# NotSoSmartWatch-BASIC-BOTTOM.net
KiCad netlist of a schematic drawn in EAGLE
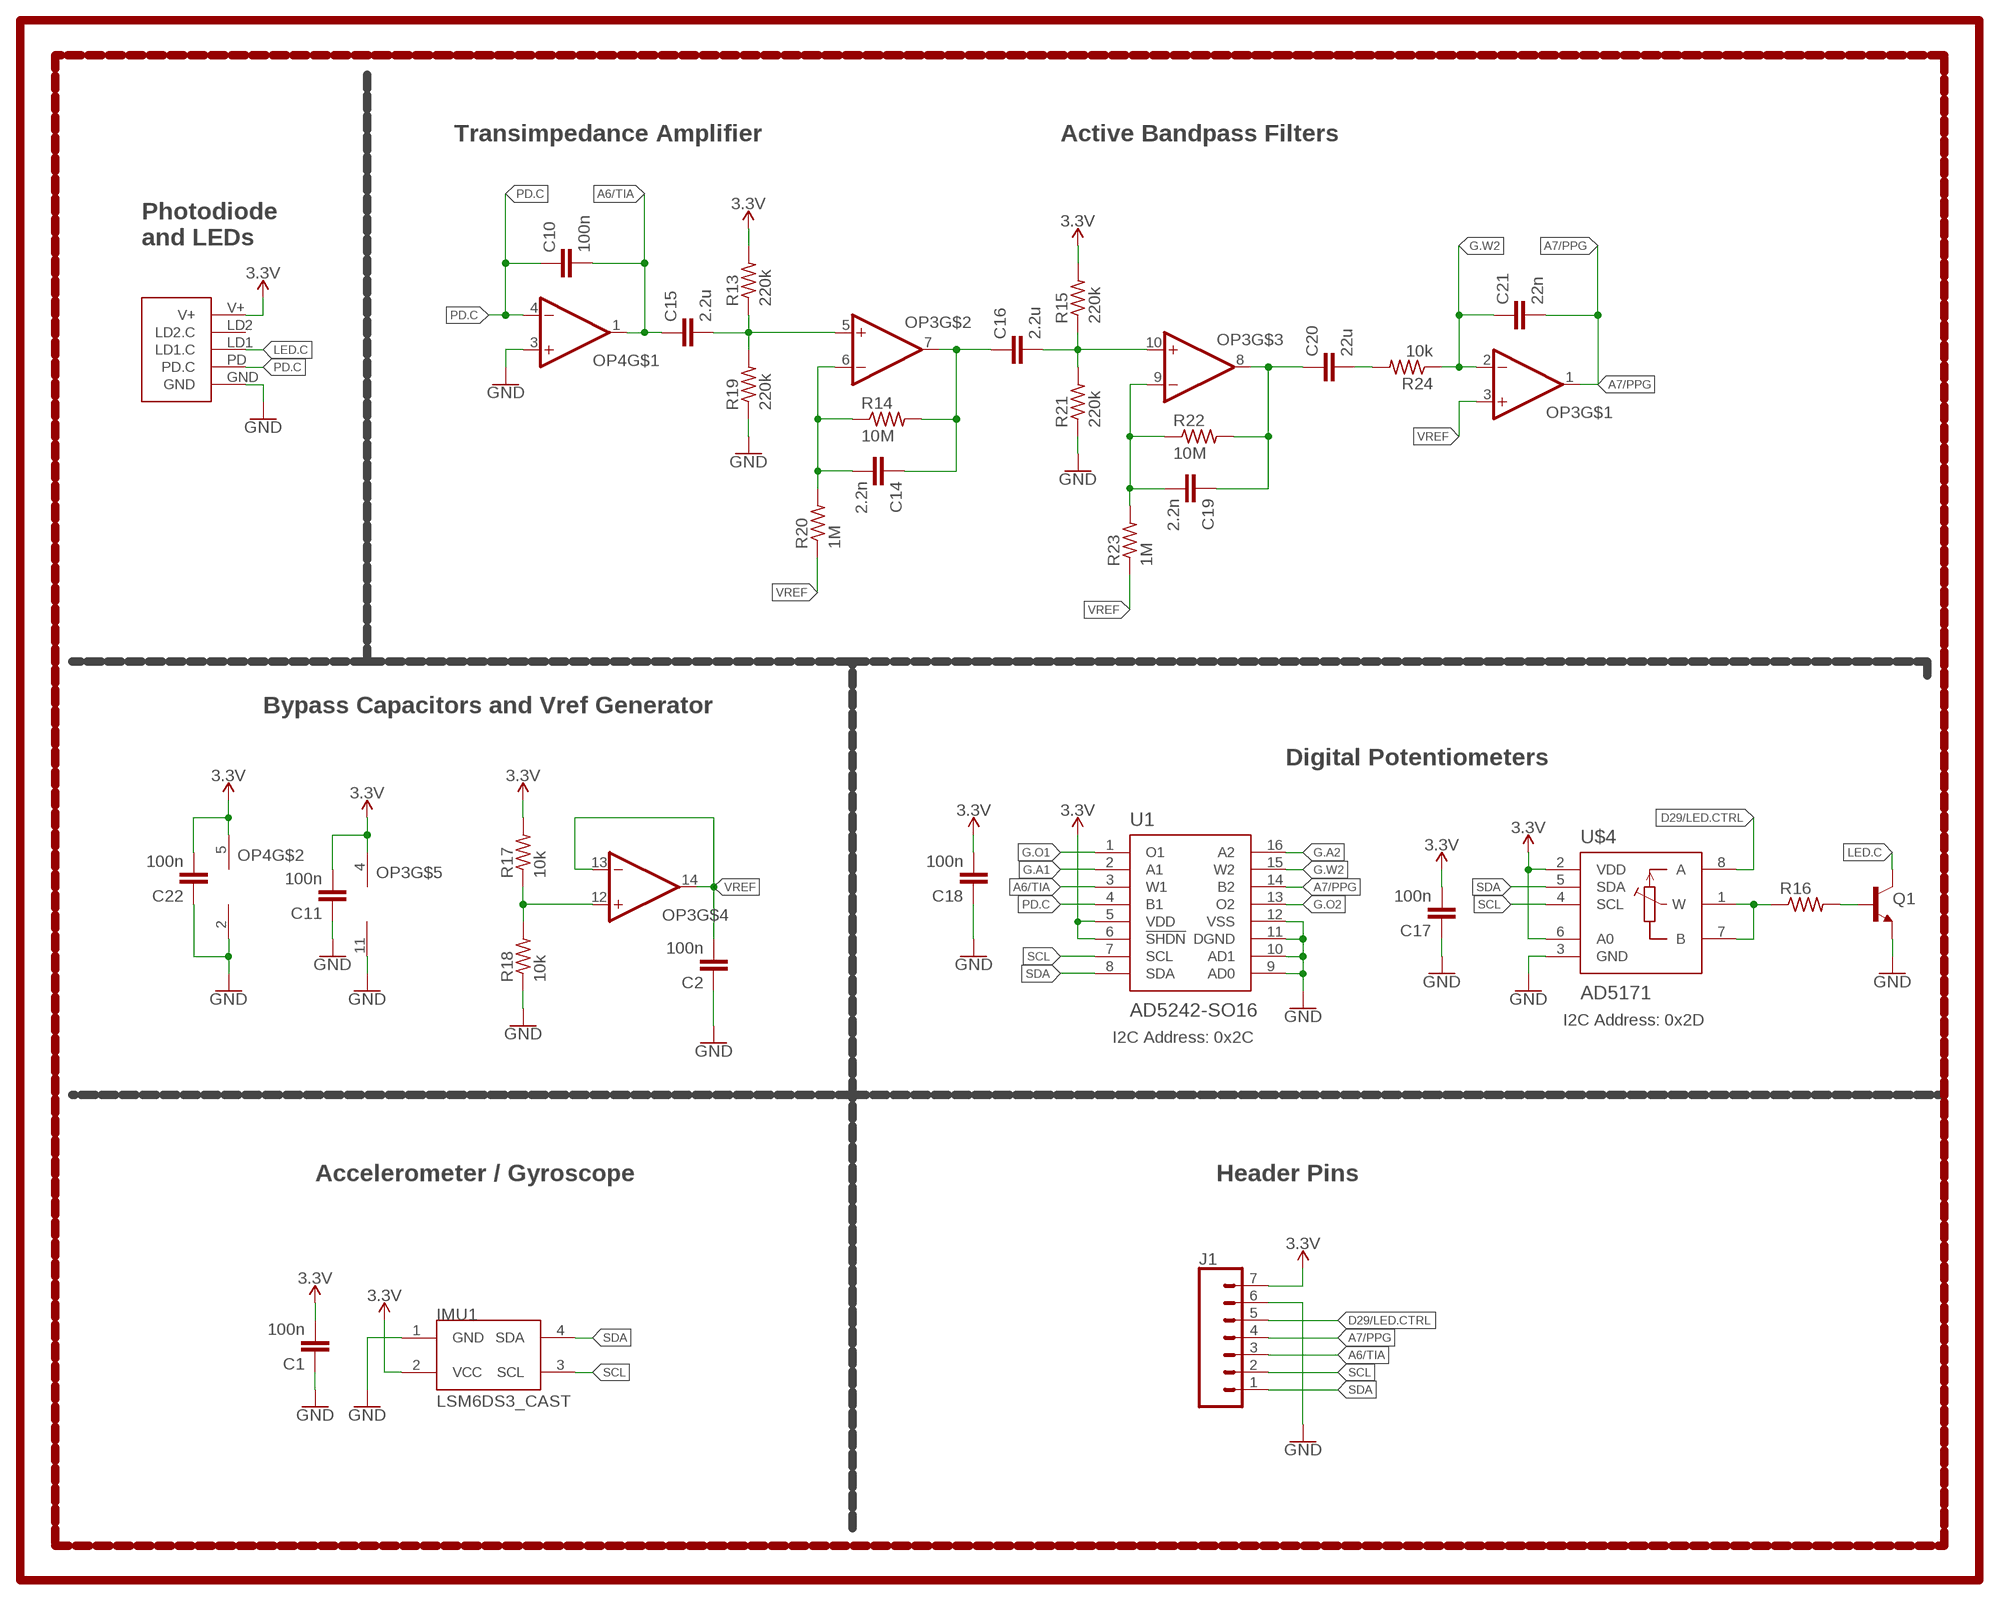
[diagram p0: schematic, sheet 1]

(export (version "E")
  (design (tool "Eeschema 10.0.6"))
  (components
    (comp (ref "C1")
      (value "100n")
      (footprint "eagle-import:C0603")
      (libsource (lib "eagle-import") (part "CAPACITOR0603"))
    )
    (comp (ref "C2")
      (value "100n")
      (footprint "eagle-import:C0603")
      (libsource (lib "eagle-import") (part "CAPACITOR0603"))
    )
    (comp (ref "C10")
      (value "100n")
      (footprint "eagle-import:C0603")
      (libsource (lib "eagle-import") (part "CAPACITOR0603"))
    )
    (comp (ref "C11")
      (value "100n")
      (footprint "eagle-import:C0603")
      (libsource (lib "eagle-import") (part "CAPACITOR0603"))
    )
    (comp (ref "C14")
      (value "2.2n")
      (footprint "eagle-import:C0603")
      (libsource (lib "eagle-import") (part "CAPACITOR0603"))
    )
    (comp (ref "C15")
      (value "2.2u")
      (footprint "eagle-import:C0603")
      (libsource (lib "eagle-import") (part "CAPACITOR0603"))
    )
    (comp (ref "C16")
      (value "2.2u")
      (footprint "eagle-import:C0603")
      (libsource (lib "eagle-import") (part "CAPACITOR0603"))
    )
    (comp (ref "C17")
      (value "100n")
      (footprint "eagle-import:C0603")
      (libsource (lib "eagle-import") (part "CAPACITOR0603"))
    )
    (comp (ref "C18")
      (value "100n")
      (footprint "eagle-import:C0603")
      (libsource (lib "eagle-import") (part "CAPACITOR0603"))
    )
    (comp (ref "C19")
      (value "2.2n")
      (footprint "eagle-import:C0603")
      (libsource (lib "eagle-import") (part "CAPACITOR0603"))
    )
    (comp (ref "C20")
      (value "22u")
      (footprint "eagle-import:C0603")
      (libsource (lib "eagle-import") (part "CAPACITOR0603"))
    )
    (comp (ref "C21")
      (value "22n")
      (footprint "eagle-import:C0603")
      (libsource (lib "eagle-import") (part "CAPACITOR0603"))
    )
    (comp (ref "C22")
      (value "100n")
      (footprint "eagle-import:C0603")
      (libsource (lib "eagle-import") (part "CAPACITOR0603"))
    )
    (comp (ref "IMU1")
      (value "LSM6DS3_CAST")
      (footprint "eagle-import:LSM6DS3_CAST")
      (libsource (lib "eagle-import") (part "LSM6DS3_CAST"))
    )
    (comp (ref "J1")
      (value "CONN_07-1.27MM")
      (footprint "eagle-import:1X07_1.27MM")
      (libsource (lib "eagle-import") (part "CONN_07-1.27MM"))
    )
    (comp (ref "OP3")
      (value "OP-QUAD-SO14")
      (footprint "eagle-import:SO14")
      (libsource (lib "eagle-import") (part "OP-QUAD-SO14"))
    )
    (comp (ref "OP4")
      (value "OP-SINGLEOT")
      (footprint "eagle-import:SOT23-5")
      (libsource (lib "eagle-import") (part "OP-SINGLEOT"))
    )
    (comp (ref "Q1")
      (value "NPN-GENERIC")
      (footprint "eagle-import:SOT23-3")
      (libsource (lib "eagle-import") (part "NPN-GENERIC"))
    )
    (comp (ref "R13")
      (value "220k")
      (footprint "eagle-import:R0603")
      (libsource (lib "eagle-import") (part "RESISTOR0603"))
    )
    (comp (ref "R14")
      (value "10M")
      (footprint "eagle-import:R0603")
      (libsource (lib "eagle-import") (part "RESISTOR0603"))
    )
    (comp (ref "R15")
      (value "220k")
      (footprint "eagle-import:R0603")
      (libsource (lib "eagle-import") (part "RESISTOR0603"))
    )
    (comp (ref "R16")
      (value "RESISTOR0603")
      (footprint "eagle-import:R0603")
      (libsource (lib "eagle-import") (part "RESISTOR0603"))
    )
    (comp (ref "R17")
      (value "10k")
      (footprint "eagle-import:R0402")
      (libsource (lib "eagle-import") (part "RESISTOR0402"))
    )
    (comp (ref "R18")
      (value "10k")
      (footprint "eagle-import:R0402")
      (libsource (lib "eagle-import") (part "RESISTOR0402"))
    )
    (comp (ref "R19")
      (value "220k")
      (footprint "eagle-import:R0603")
      (libsource (lib "eagle-import") (part "RESISTOR0603"))
    )
    (comp (ref "R20")
      (value "1M")
      (footprint "eagle-import:R0603")
      (libsource (lib "eagle-import") (part "RESISTOR0603"))
    )
    (comp (ref "R21")
      (value "220k")
      (footprint "eagle-import:R0603")
      (libsource (lib "eagle-import") (part "RESISTOR0603"))
    )
    (comp (ref "R22")
      (value "10M")
      (footprint "eagle-import:R0603")
      (libsource (lib "eagle-import") (part "RESISTOR0603"))
    )
    (comp (ref "R23")
      (value "1M")
      (footprint "eagle-import:R0603")
      (libsource (lib "eagle-import") (part "RESISTOR0603"))
    )
    (comp (ref "R24")
      (value "10k")
      (footprint "eagle-import:R0603")
      (libsource (lib "eagle-import") (part "RESISTOR0603"))
    )
    (comp (ref "U$3")
      (value "PPG.MODULE.2")
      (footprint "eagle-import:PPG.MODULE.2")
      (libsource (lib "eagle-import") (part "PPG.MODULE.2"))
    )
    (comp (ref "U$4")
      (value "AD5171")
      (footprint "eagle-import:SOT-23-8")
      (libsource (lib "eagle-import") (part "AD5171"))
    )
    (comp (ref "U1")
      (value "AD5242-SO16")
      (footprint "eagle-import:SO16")
      (libsource (lib "eagle-import") (part "AD5242-SO16"))
    )
  )
  (nets
    (net (code "1") (name "3.3V") (class "Default")
      (node (ref "C1") (pin "2") (pinfunction "2_2") (pintype "passive"))
      (node (ref "C11") (pin "2") (pinfunction "2_2") (pintype "passive"))
      (node (ref "C17") (pin "2") (pinfunction "2_2") (pintype "passive"))
      (node (ref "C18") (pin "2") (pinfunction "2_2") (pintype "passive"))
      (node (ref "C22") (pin "2") (pinfunction "2_2") (pintype "passive"))
      (node (ref "IMU1") (pin "2") (pinfunction "VCC_2") (pintype "bidirectional"))
      (node (ref "J1") (pin "7") (pinfunction "7_7") (pintype "passive"))
      (node (ref "OP3") (pin "4") (pinfunction "V+_4") (pintype "power_in"))
      (node (ref "OP4") (pin "5") (pinfunction "V+_5") (pintype "power_in"))
      (node (ref "R13") (pin "2") (pinfunction "2_2") (pintype "passive"))
      (node (ref "R15") (pin "2") (pinfunction "2_2") (pintype "passive"))
      (node (ref "R17") (pin "2") (pinfunction "2_2") (pintype "passive"))
      (node (ref "U$3") (pin "V+") (pinfunction "V+_V+") (pintype "bidirectional"))
      (node (ref "U$4") (pin "2") (pinfunction "VDD_2") (pintype "bidirectional"))
      (node (ref "U$4") (pin "6") (pinfunction "A0_6") (pintype "bidirectional"))
      (node (ref "U1") (pin "5") (pinfunction "VDD_5") (pintype "bidirectional"))
      (node (ref "U1") (pin "6") (pinfunction "~{SHDN}_6") (pintype "bidirectional"))
    )
    (net (code "2") (name "A6{slash}TIA") (class "Default")
      (node (ref "C10") (pin "2") (pinfunction "2_2") (pintype "passive"))
      (node (ref "C15") (pin "1") (pinfunction "1_1") (pintype "passive"))
      (node (ref "J1") (pin "3") (pinfunction "3_3") (pintype "passive"))
      (node (ref "OP4") (pin "1") (pinfunction "OUT_1") (pintype "output"))
      (node (ref "U1") (pin "3") (pinfunction "W1_3") (pintype "bidirectional"))
    )
    (net (code "3") (name "A7{slash}PPG") (class "Default")
      (node (ref "C21") (pin "2") (pinfunction "2_2") (pintype "passive"))
      (node (ref "J1") (pin "4") (pinfunction "4_4") (pintype "passive"))
      (node (ref "OP3") (pin "1") (pinfunction "OUT_1") (pintype "output"))
      (node (ref "U1") (pin "14") (pinfunction "B2_14") (pintype "bidirectional"))
    )
    (net (code "4") (name "D29{slash}LED.CTRL") (class "Default")
      (node (ref "J1") (pin "5") (pinfunction "5_5") (pintype "passive"))
      (node (ref "U$4") (pin "8") (pinfunction "A_8") (pintype "bidirectional"))
    )
    (net (code "5") (name "G.A1") (class "Default")
      (node (ref "U1") (pin "2") (pinfunction "A1_2") (pintype "bidirectional"))
    )
    (net (code "6") (name "G.A2") (class "Default")
      (node (ref "U1") (pin "16") (pinfunction "A2_16") (pintype "bidirectional"))
    )
    (net (code "7") (name "G.O1") (class "Default")
      (node (ref "U1") (pin "1") (pinfunction "O1_1") (pintype "bidirectional"))
    )
    (net (code "8") (name "G.O2") (class "Default")
      (node (ref "U1") (pin "13") (pinfunction "O2_13") (pintype "bidirectional"))
    )
    (net (code "9") (name "G.W2") (class "Default")
      (node (ref "C21") (pin "1") (pinfunction "1_1") (pintype "passive"))
      (node (ref "OP3") (pin "2") (pinfunction "-IN_2") (pintype "input"))
      (node (ref "R24") (pin "1") (pinfunction "1_1") (pintype "passive"))
      (node (ref "U1") (pin "15") (pinfunction "W2_15") (pintype "bidirectional"))
    )
    (net (code "10") (name "GND") (class "Default")
      (node (ref "C1") (pin "1") (pinfunction "1_1") (pintype "passive"))
      (node (ref "C11") (pin "1") (pinfunction "1_1") (pintype "passive"))
      (node (ref "C17") (pin "1") (pinfunction "1_1") (pintype "passive"))
      (node (ref "C18") (pin "1") (pinfunction "1_1") (pintype "passive"))
      (node (ref "C2") (pin "1") (pinfunction "1_1") (pintype "passive"))
      (node (ref "C22") (pin "1") (pinfunction "1_1") (pintype "passive"))
      (node (ref "IMU1") (pin "1") (pinfunction "GND_1") (pintype "bidirectional"))
      (node (ref "J1") (pin "6") (pinfunction "6_6") (pintype "passive"))
      (node (ref "OP3") (pin "11") (pinfunction "V-_11") (pintype "power_in"))
      (node (ref "OP4") (pin "2") (pinfunction "V-_2") (pintype "power_in"))
      (node (ref "OP4") (pin "3") (pinfunction "+IN_3") (pintype "input"))
      (node (ref "Q1") (pin "2") (pinfunction "E_2") (pintype "passive"))
      (node (ref "R18") (pin "1") (pinfunction "1_1") (pintype "passive"))
      (node (ref "R19") (pin "1") (pinfunction "1_1") (pintype "passive"))
      (node (ref "R21") (pin "1") (pinfunction "1_1") (pintype "passive"))
      (node (ref "U$3") (pin "GND") (pinfunction "GND_GND") (pintype "bidirectional"))
      (node (ref "U$4") (pin "3") (pinfunction "GND_3") (pintype "bidirectional"))
      (node (ref "U1") (pin "10") (pinfunction "AD1_10") (pintype "bidirectional"))
      (node (ref "U1") (pin "11") (pinfunction "DGND_11") (pintype "bidirectional"))
      (node (ref "U1") (pin "12") (pinfunction "VSS_12") (pintype "bidirectional"))
      (node (ref "U1") (pin "9") (pinfunction "AD0_9") (pintype "bidirectional"))
    )
    (net (code "11") (name "LED.C") (class "Default")
      (node (ref "Q1") (pin "3") (pinfunction "C_3") (pintype "passive"))
      (node (ref "U$3") (pin "LD1") (pinfunction "LD1.C_LD1") (pintype "bidirectional"))
    )
    (net (code "12") (name "Net-(C20-Pad2)") (class "Default")
      (node (ref "C20") (pin "2") (pinfunction "2_2") (pintype "passive"))
      (node (ref "R24") (pin "2") (pinfunction "2_2") (pintype "passive"))
    )
    (net (code "13") (name "Net-(OP3B-+IN)") (class "Default")
      (node (ref "C15") (pin "2") (pinfunction "2_2") (pintype "passive"))
      (node (ref "OP3") (pin "5") (pinfunction "+IN_5") (pintype "input"))
      (node (ref "R13") (pin "1") (pinfunction "1_1") (pintype "passive"))
      (node (ref "R19") (pin "2") (pinfunction "2_2") (pintype "passive"))
    )
    (net (code "14") (name "Net-(OP3B--IN)") (class "Default")
      (node (ref "C14") (pin "2") (pinfunction "2_2") (pintype "passive"))
      (node (ref "OP3") (pin "6") (pinfunction "-IN_6") (pintype "input"))
      (node (ref "R14") (pin "1") (pinfunction "1_1") (pintype "passive"))
      (node (ref "R20") (pin "2") (pinfunction "2_2") (pintype "passive"))
    )
    (net (code "15") (name "Net-(OP3B-OUT)") (class "Default")
      (node (ref "C14") (pin "1") (pinfunction "1_1") (pintype "passive"))
      (node (ref "C16") (pin "1") (pinfunction "1_1") (pintype "passive"))
      (node (ref "OP3") (pin "7") (pinfunction "OUT_7") (pintype "output"))
      (node (ref "R14") (pin "2") (pinfunction "2_2") (pintype "passive"))
    )
    (net (code "16") (name "Net-(OP3C-+IN)") (class "Default")
      (node (ref "C16") (pin "2") (pinfunction "2_2") (pintype "passive"))
      (node (ref "OP3") (pin "10") (pinfunction "+IN_10") (pintype "input"))
      (node (ref "R15") (pin "1") (pinfunction "1_1") (pintype "passive"))
      (node (ref "R21") (pin "2") (pinfunction "2_2") (pintype "passive"))
    )
    (net (code "17") (name "Net-(OP3C--IN)") (class "Default")
      (node (ref "C19") (pin "2") (pinfunction "2_2") (pintype "passive"))
      (node (ref "OP3") (pin "9") (pinfunction "-IN_9") (pintype "input"))
      (node (ref "R22") (pin "1") (pinfunction "1_1") (pintype "passive"))
      (node (ref "R23") (pin "2") (pinfunction "2_2") (pintype "passive"))
    )
    (net (code "18") (name "Net-(OP3C-OUT)") (class "Default")
      (node (ref "C19") (pin "1") (pinfunction "1_1") (pintype "passive"))
      (node (ref "C20") (pin "1") (pinfunction "1_1") (pintype "passive"))
      (node (ref "OP3") (pin "8") (pinfunction "OUT_8") (pintype "output"))
      (node (ref "R22") (pin "2") (pinfunction "2_2") (pintype "passive"))
    )
    (net (code "19") (name "Net-(OP3D-+IN)") (class "Default")
      (node (ref "OP3") (pin "12") (pinfunction "+IN_12") (pintype "input"))
      (node (ref "R17") (pin "1") (pinfunction "1_1") (pintype "passive"))
      (node (ref "R18") (pin "2") (pinfunction "2_2") (pintype "passive"))
    )
    (net (code "20") (name "Net-(Q1-B)") (class "Default")
      (node (ref "Q1") (pin "1") (pinfunction "B_1") (pintype "passive"))
      (node (ref "R16") (pin "2") (pinfunction "2_2") (pintype "passive"))
    )
    (net (code "21") (name "Net-(U$4-B)") (class "Default")
      (node (ref "R16") (pin "1") (pinfunction "1_1") (pintype "passive"))
      (node (ref "U$4") (pin "1") (pinfunction "W_1") (pintype "bidirectional"))
      (node (ref "U$4") (pin "7") (pinfunction "B_7") (pintype "bidirectional"))
    )
    (net (code "22") (name "PD.C") (class "Default")
      (node (ref "C10") (pin "1") (pinfunction "1_1") (pintype "passive"))
      (node (ref "OP4") (pin "4") (pinfunction "-IN_4") (pintype "input"))
      (node (ref "U$3") (pin "PD") (pinfunction "PD.C_PD") (pintype "bidirectional"))
      (node (ref "U1") (pin "4") (pinfunction "B1_4") (pintype "bidirectional"))
    )
    (net (code "23") (name "SCL") (class "Default")
      (node (ref "IMU1") (pin "3") (pinfunction "SCL_3") (pintype "bidirectional"))
      (node (ref "J1") (pin "2") (pinfunction "2_2") (pintype "passive"))
      (node (ref "U$4") (pin "4") (pinfunction "SCL_4") (pintype "bidirectional"))
      (node (ref "U1") (pin "7") (pinfunction "SCL_7") (pintype "bidirectional"))
    )
    (net (code "24") (name "SDA") (class "Default")
      (node (ref "IMU1") (pin "4") (pinfunction "SDA_4") (pintype "bidirectional"))
      (node (ref "J1") (pin "1") (pinfunction "1_1") (pintype "passive"))
      (node (ref "U$4") (pin "5") (pinfunction "SDA_5") (pintype "bidirectional"))
      (node (ref "U1") (pin "8") (pinfunction "SDA_8") (pintype "bidirectional"))
    )
    (net (code "25") (name "VREF") (class "Default")
      (node (ref "C2") (pin "2") (pinfunction "2_2") (pintype "passive"))
      (node (ref "OP3") (pin "13") (pinfunction "-IN_13") (pintype "input"))
      (node (ref "OP3") (pin "14") (pinfunction "OUT_14") (pintype "output"))
      (node (ref "OP3") (pin "3") (pinfunction "+IN_3") (pintype "input"))
      (node (ref "R20") (pin "1") (pinfunction "1_1") (pintype "passive"))
      (node (ref "R23") (pin "1") (pinfunction "1_1") (pintype "passive"))
    )
    (net (code "26") (name "unconnected-(U$3-LD2.C-PadLD2)") (class "Default")
      (node (ref "U$3") (pin "LD2") (pinfunction "LD2.C_LD2") (pintype "bidirectional"))
    )
  )
)
